# arm_controller_single.net
KiCad netlist of a schematic drawn in EAGLE
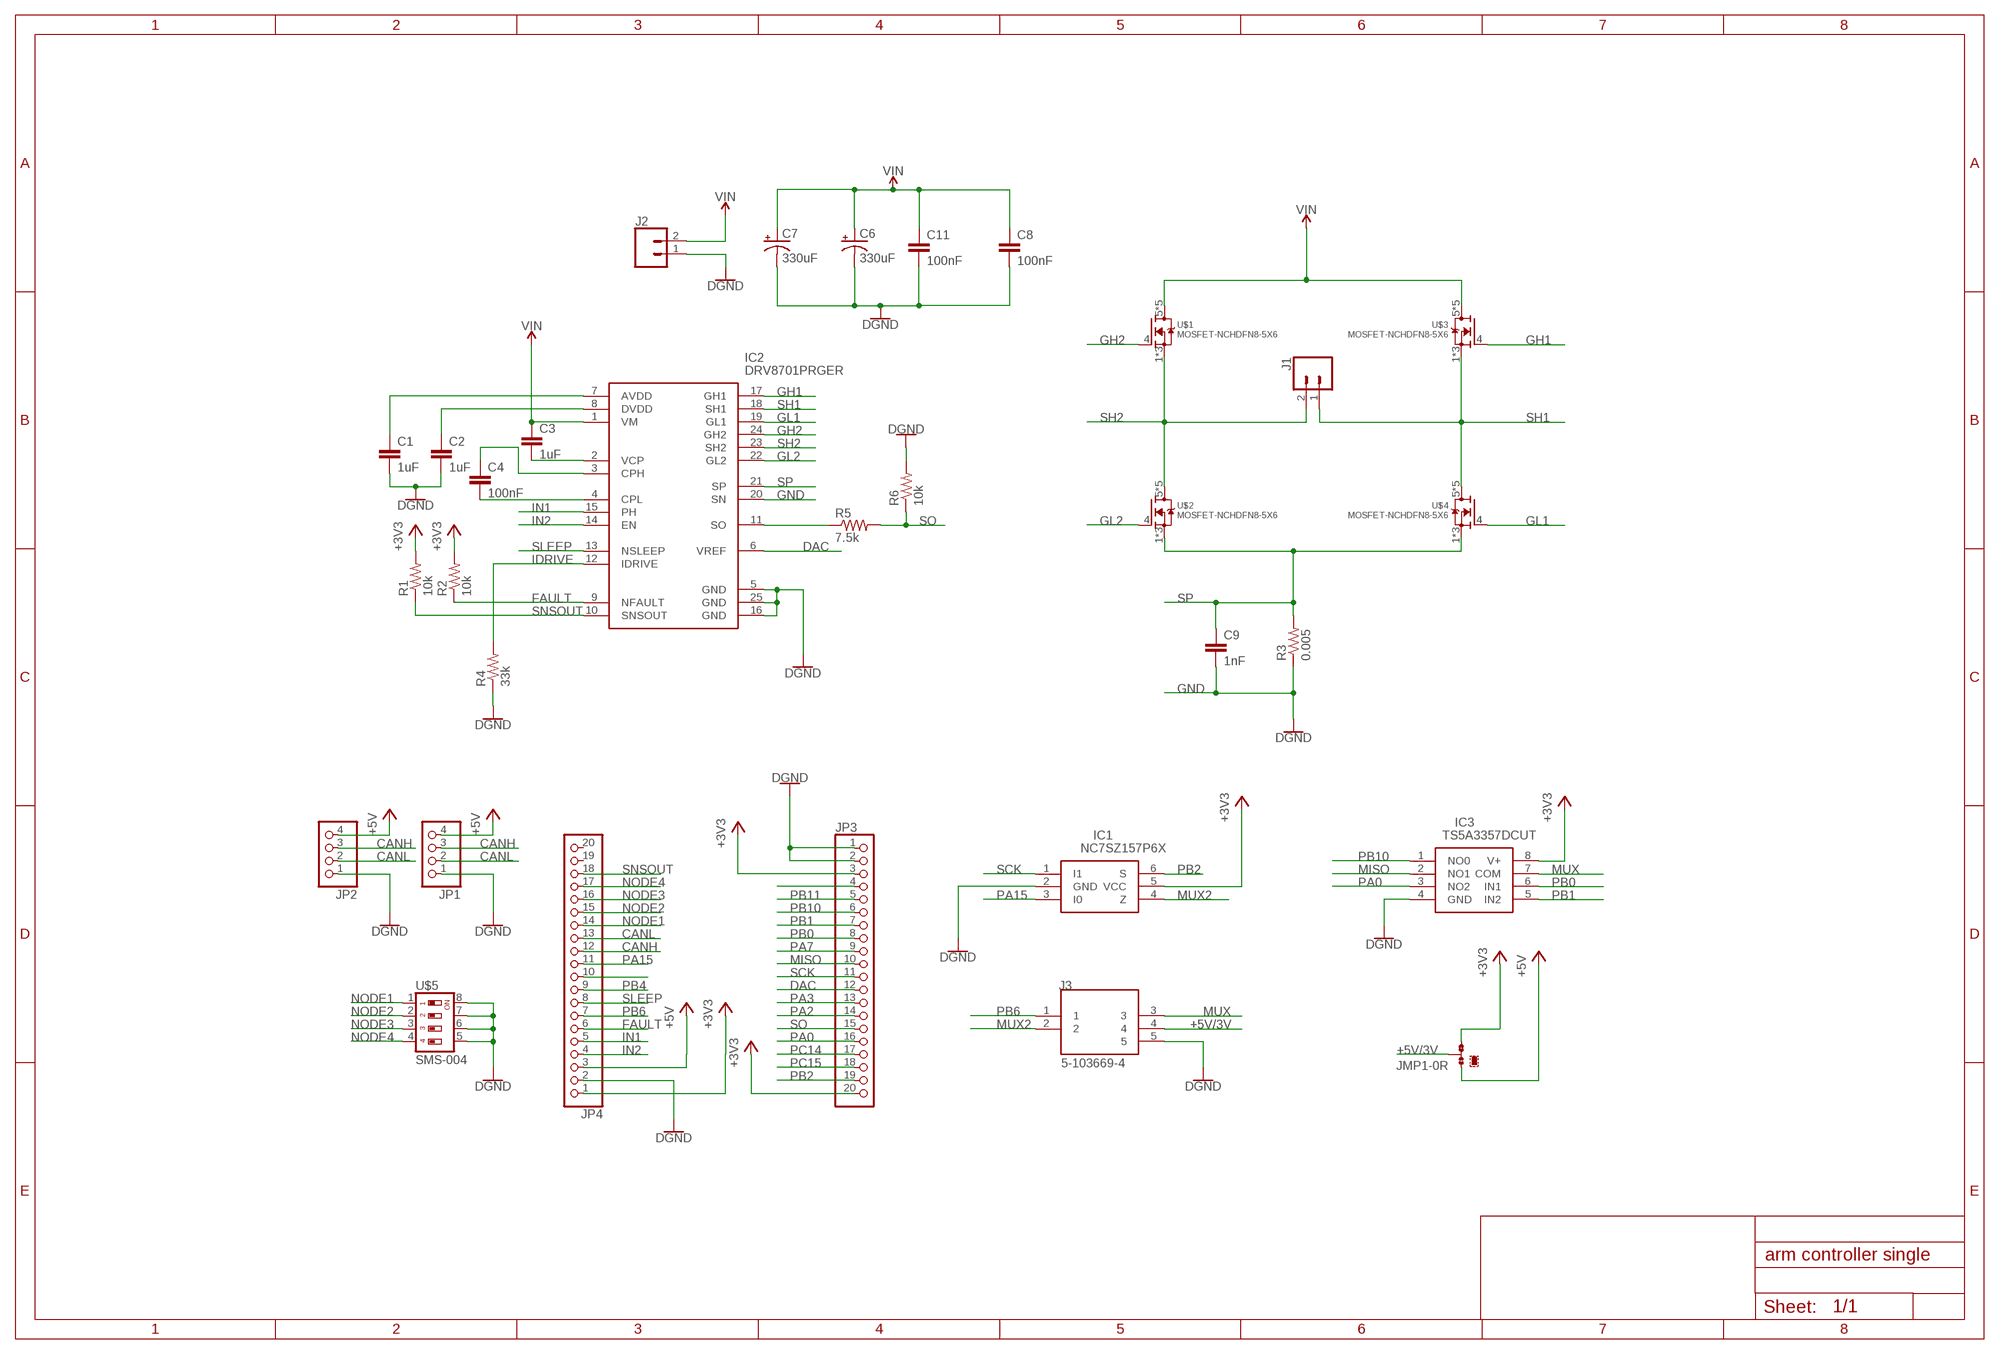
[diagram p0: schematic, sheet 1]

(export (version "E")
  (design (tool "Eeschema 10.0.6"))
  (components
    (comp (ref "C1")
      (value "1uF")
      (footprint "eagle-import:C0805")
      (libsource (lib "eagle-import") (part "C-EUC0805"))
    )
    (comp (ref "C2")
      (value "1uF")
      (footprint "eagle-import:C0805")
      (libsource (lib "eagle-import") (part "C-EUC0805"))
    )
    (comp (ref "C3")
      (value "1uF")
      (footprint "eagle-import:C0805")
      (libsource (lib "eagle-import") (part "C-EUC0805"))
    )
    (comp (ref "C4")
      (value "100nF")
      (footprint "eagle-import:C0805")
      (libsource (lib "eagle-import") (part "C-EUC0805"))
    )
    (comp (ref "C6")
      (value "330uF")
      (footprint "eagle-import:140CLH-1010")
      (libsource (lib "eagle-import") (part "CPOL-US140CLH-1010"))
    )
    (comp (ref "C7")
      (value "330uF")
      (footprint "eagle-import:140CLH-1010")
      (libsource (lib "eagle-import") (part "CPOL-US140CLH-1010"))
    )
    (comp (ref "C8")
      (value "100nF")
      (footprint "eagle-import:C0805")
      (libsource (lib "eagle-import") (part "C-EUC0805"))
    )
    (comp (ref "C9")
      (value "1nF")
      (footprint "eagle-import:C0805")
      (libsource (lib "eagle-import") (part "C-EUC0805"))
    )
    (comp (ref "C11")
      (value "100nF")
      (footprint "eagle-import:C0805")
      (libsource (lib "eagle-import") (part "C-EUC0805"))
    )
    (comp (ref "IC1")
      (value "NC7SZ157P6X")
      (footprint "eagle-import:SOT65P210X110-6N")
      (fields (field (name "MOUSER_PART_NUMBER") "512-NC7SZ157P6X"))
      (libsource (lib "eagle-import") (part "NC7SZ157P6X"))
    )
    (comp (ref "IC2")
      (value "DRV8701PRGER")
      (footprint "eagle-import:QFN50P400X400X100-25N")
      (fields (field (name "MOUSER_PART_NUMBER") "595-DRV8701PRGER"))
      (libsource (lib "eagle-import") (part "DRV8701PRGER"))
    )
    (comp (ref "IC3")
      (value "TS5A3357DCUT")
      (footprint "eagle-import:SOP50P310X90-8N")
      (fields (field (name "MOUSER_PART_NUMBER") "595-TS5A3357DCUT"))
      (libsource (lib "eagle-import") (part "TS5A3357DCUT"))
    )
    (comp (ref "J1")
      (value "CONN_025MM")
      (footprint "eagle-import:SCREWTERMINAL-5MM-2")
      (libsource (lib "eagle-import") (part "CONN_025MM"))
    )
    (comp (ref "J2")
      (value "CONN_025MM")
      (footprint "eagle-import:SCREWTERMINAL-5MM-2")
      (libsource (lib "eagle-import") (part "CONN_025MM"))
    )
    (comp (ref "J3")
      (value "5-103669-4")
      (footprint "eagle-import:TE_5-103669-4")
      (fields (field (name "MF") "TE Connectivity"))
      (libsource (lib "eagle-import") (part "5-103669-4"))
    )
    (comp (ref "JMP1")
      (value "0R-JUMPB")
      (footprint "eagle-import:B0R-JMP")
      (libsource (lib "eagle-import") (part "0R-JUMPB"))
    )
    (comp (ref "JP1")
      (value "PINHD-1X4")
      (footprint "eagle-import:1X04")
      (libsource (lib "eagle-import") (part "PINHD-1X4"))
    )
    (comp (ref "JP2")
      (value "PINHD-1X4")
      (footprint "eagle-import:1X04")
      (libsource (lib "eagle-import") (part "PINHD-1X4"))
    )
    (comp (ref "JP3")
      (value "PINHD-1X20")
      (footprint "eagle-import:1X20")
      (libsource (lib "eagle-import") (part "PINHD-1X20"))
    )
    (comp (ref "JP4")
      (value "PINHD-1X20")
      (footprint "eagle-import:1X20")
      (libsource (lib "eagle-import") (part "PINHD-1X20"))
    )
    (comp (ref "R1")
      (value "10k")
      (footprint "eagle-import:M0805")
      (libsource (lib "eagle-import") (part "R-US_M0805"))
    )
    (comp (ref "R2")
      (value "10k")
      (footprint "eagle-import:M0805")
      (libsource (lib "eagle-import") (part "R-US_M0805"))
    )
    (comp (ref "R3")
      (value "0.005")
      (footprint "eagle-import:WSC4527")
      (libsource (lib "eagle-import") (part "R-US_WSC4527"))
    )
    (comp (ref "R4")
      (value "33k")
      (footprint "eagle-import:M0805")
      (libsource (lib "eagle-import") (part "R-US_M0805"))
    )
    (comp (ref "R5")
      (value "7.5k")
      (footprint "eagle-import:M0805")
      (libsource (lib "eagle-import") (part "R-US_M0805"))
    )
    (comp (ref "R6")
      (value "10k")
      (footprint "eagle-import:M0805")
      (libsource (lib "eagle-import") (part "R-US_M0805"))
    )
    (comp (ref "U$1")
      (value "MOSFET-NCHDFN8-5X6")
      (footprint "eagle-import:ALOM_DFN5X6_8L_EP1_P")
      (libsource (lib "eagle-import") (part "MOSFET-NCHDFN8-5X6"))
    )
    (comp (ref "U$2")
      (value "MOSFET-NCHDFN8-5X6")
      (footprint "eagle-import:ALOM_DFN5X6_8L_EP1_P")
      (libsource (lib "eagle-import") (part "MOSFET-NCHDFN8-5X6"))
    )
    (comp (ref "U$3")
      (value "MOSFET-NCHDFN8-5X6")
      (footprint "eagle-import:ALOM_DFN5X6_8L_EP1_P")
      (libsource (lib "eagle-import") (part "MOSFET-NCHDFN8-5X6"))
    )
    (comp (ref "U$4")
      (value "MOSFET-NCHDFN8-5X6")
      (footprint "eagle-import:ALOM_DFN5X6_8L_EP1_P")
      (libsource (lib "eagle-import") (part "MOSFET-NCHDFN8-5X6"))
    )
    (comp (ref "U$5")
      (value "SMS-004")
      (footprint "eagle-import:SMS-004")
      (libsource (lib "eagle-import") (part "SMS-004"))
    )
  )
  (nets
    (net (code "1") (name "+3V3") (class "Default")
      (node (ref "IC1") (pin "5") (pinfunction "VCC_5") (pintype "power_in"))
      (node (ref "IC3") (pin "8") (pinfunction "V+_8") (pintype "bidirectional"))
      (node (ref "JMP1") (pin "3") (pinfunction "3_3") (pintype "passive"))
      (node (ref "JP3") (pin "20") (pinfunction "20_20") (pintype "passive"))
      (node (ref "JP3") (pin "3") (pinfunction "3_3") (pintype "passive"))
      (node (ref "JP4") (pin "1") (pinfunction "1_1") (pintype "passive"))
      (node (ref "R1") (pin "2") (pinfunction "2_2") (pintype "passive"))
      (node (ref "R2") (pin "2") (pinfunction "2_2") (pintype "passive"))
    )
    (net (code "2") (name "+5V") (class "Default")
      (node (ref "JMP1") (pin "1") (pinfunction "1_1") (pintype "passive"))
      (node (ref "JP1") (pin "4") (pinfunction "4_4") (pintype "passive"))
      (node (ref "JP2") (pin "4") (pinfunction "4_4") (pintype "passive"))
      (node (ref "JP4") (pin "3") (pinfunction "3_3") (pintype "passive"))
    )
    (net (code "3") (name "/+5V{slash}3V") (class "Default")
      (node (ref "J3") (pin "4") (pinfunction "4_4") (pintype "passive"))
      (node (ref "JMP1") (pin "2") (pinfunction "2_2") (pintype "passive"))
    )
    (net (code "4") (name "/CANH") (class "Default")
      (node (ref "JP1") (pin "3") (pinfunction "3_3") (pintype "passive"))
      (node (ref "JP2") (pin "3") (pinfunction "3_3") (pintype "passive"))
      (node (ref "JP4") (pin "12") (pinfunction "12_12") (pintype "passive"))
    )
    (net (code "5") (name "/CANL") (class "Default")
      (node (ref "JP1") (pin "2") (pinfunction "2_2") (pintype "passive"))
      (node (ref "JP2") (pin "2") (pinfunction "2_2") (pintype "passive"))
      (node (ref "JP4") (pin "13") (pinfunction "13_13") (pintype "passive"))
    )
    (net (code "6") (name "/DAC") (class "Default")
      (node (ref "IC2") (pin "6") (pinfunction "VREF_6") (pintype "bidirectional"))
      (node (ref "JP3") (pin "12") (pinfunction "12_12") (pintype "passive"))
    )
    (net (code "7") (name "/FAULT") (class "Default")
      (node (ref "IC2") (pin "9") (pinfunction "NFAULT_9") (pintype "bidirectional"))
      (node (ref "JP4") (pin "6") (pinfunction "6_6") (pintype "passive"))
      (node (ref "R2") (pin "1") (pinfunction "1_1") (pintype "passive"))
    )
    (net (code "8") (name "/GH1") (class "Default")
      (node (ref "IC2") (pin "17") (pinfunction "GH1_17") (pintype "bidirectional"))
      (node (ref "U$3") (pin "4") (pinfunction "G_4") (pintype "bidirectional"))
    )
    (net (code "9") (name "/GH2") (class "Default")
      (node (ref "IC2") (pin "24") (pinfunction "GH2_24") (pintype "bidirectional"))
      (node (ref "U$1") (pin "4") (pinfunction "G_4") (pintype "bidirectional"))
    )
    (net (code "10") (name "/GL1") (class "Default")
      (node (ref "IC2") (pin "19") (pinfunction "GL1_19") (pintype "bidirectional"))
      (node (ref "U$4") (pin "4") (pinfunction "G_4") (pintype "bidirectional"))
    )
    (net (code "11") (name "/GL2") (class "Default")
      (node (ref "IC2") (pin "22") (pinfunction "GL2_22") (pintype "bidirectional"))
      (node (ref "U$2") (pin "4") (pinfunction "G_4") (pintype "bidirectional"))
    )
    (net (code "12") (name "/IDRIVE") (class "Default")
      (node (ref "IC2") (pin "12") (pinfunction "IDRIVE_12") (pintype "bidirectional"))
      (node (ref "R4") (pin "2") (pinfunction "2_2") (pintype "passive"))
    )
    (net (code "13") (name "/IN1") (class "Default")
      (node (ref "IC2") (pin "15") (pinfunction "PH_15") (pintype "bidirectional"))
      (node (ref "JP4") (pin "5") (pinfunction "5_5") (pintype "passive"))
    )
    (net (code "14") (name "/IN2") (class "Default")
      (node (ref "IC2") (pin "14") (pinfunction "EN_14") (pintype "bidirectional"))
      (node (ref "JP4") (pin "4") (pinfunction "4_4") (pintype "passive"))
    )
    (net (code "15") (name "/MISO") (class "Default")
      (node (ref "IC3") (pin "2") (pinfunction "NO1_2") (pintype "bidirectional"))
      (node (ref "JP3") (pin "10") (pinfunction "10_10") (pintype "passive"))
    )
    (net (code "16") (name "/MUX") (class "Default")
      (node (ref "IC3") (pin "7") (pinfunction "COM_7") (pintype "bidirectional"))
      (node (ref "J3") (pin "3") (pinfunction "3_3") (pintype "passive"))
    )
    (net (code "17") (name "/MUX2") (class "Default")
      (node (ref "IC1") (pin "4") (pinfunction "Z_4") (pintype "output"))
      (node (ref "J3") (pin "2") (pinfunction "2_2") (pintype "passive"))
    )
    (net (code "18") (name "/NODE1") (class "Default")
      (node (ref "JP4") (pin "14") (pinfunction "14_14") (pintype "passive"))
      (node (ref "U$5") (pin "1") (pinfunction "1_1") (pintype "passive"))
    )
    (net (code "19") (name "/NODE2") (class "Default")
      (node (ref "JP4") (pin "15") (pinfunction "15_15") (pintype "passive"))
      (node (ref "U$5") (pin "2") (pinfunction "2_2") (pintype "passive"))
    )
    (net (code "20") (name "/NODE3") (class "Default")
      (node (ref "JP4") (pin "16") (pinfunction "16_16") (pintype "passive"))
      (node (ref "U$5") (pin "3") (pinfunction "3_3") (pintype "passive"))
    )
    (net (code "21") (name "/NODE4") (class "Default")
      (node (ref "JP4") (pin "17") (pinfunction "17_17") (pintype "passive"))
      (node (ref "U$5") (pin "4") (pinfunction "4_4") (pintype "passive"))
    )
    (net (code "22") (name "/PA0") (class "Default")
      (node (ref "IC3") (pin "3") (pinfunction "NO2_3") (pintype "bidirectional"))
      (node (ref "JP3") (pin "16") (pinfunction "16_16") (pintype "passive"))
    )
    (net (code "23") (name "/PA2") (class "Default")
      (node (ref "JP3") (pin "14") (pinfunction "14_14") (pintype "passive"))
    )
    (net (code "24") (name "/PA3") (class "Default")
      (node (ref "JP3") (pin "13") (pinfunction "13_13") (pintype "passive"))
    )
    (net (code "25") (name "/PA7") (class "Default")
      (node (ref "JP3") (pin "9") (pinfunction "9_9") (pintype "passive"))
    )
    (net (code "26") (name "/PA15") (class "Default")
      (node (ref "IC1") (pin "3") (pinfunction "I0_3") (pintype "input"))
      (node (ref "JP4") (pin "11") (pinfunction "11_11") (pintype "passive"))
    )
    (net (code "27") (name "/PB0") (class "Default")
      (node (ref "IC3") (pin "6") (pinfunction "IN1_6") (pintype "input"))
      (node (ref "JP3") (pin "8") (pinfunction "8_8") (pintype "passive"))
    )
    (net (code "28") (name "/PB1") (class "Default")
      (node (ref "IC3") (pin "5") (pinfunction "IN2_5") (pintype "input"))
      (node (ref "JP3") (pin "7") (pinfunction "7_7") (pintype "passive"))
    )
    (net (code "29") (name "/PB2") (class "Default")
      (node (ref "IC1") (pin "6") (pinfunction "S_6") (pintype "input"))
      (node (ref "JP3") (pin "19") (pinfunction "19_19") (pintype "passive"))
    )
    (net (code "30") (name "/PB4") (class "Default")
      (node (ref "JP4") (pin "9") (pinfunction "9_9") (pintype "passive"))
    )
    (net (code "31") (name "/PB6") (class "Default")
      (node (ref "J3") (pin "1") (pinfunction "1_1") (pintype "passive"))
      (node (ref "JP4") (pin "7") (pinfunction "7_7") (pintype "passive"))
    )
    (net (code "32") (name "/PB10") (class "Default")
      (node (ref "IC3") (pin "1") (pinfunction "NO0_1") (pintype "bidirectional"))
      (node (ref "JP3") (pin "6") (pinfunction "6_6") (pintype "passive"))
    )
    (net (code "33") (name "/PB11") (class "Default")
      (node (ref "JP3") (pin "5") (pinfunction "5_5") (pintype "passive"))
    )
    (net (code "34") (name "/PC14") (class "Default")
      (node (ref "JP3") (pin "17") (pinfunction "17_17") (pintype "passive"))
    )
    (net (code "35") (name "/PC15") (class "Default")
      (node (ref "JP3") (pin "18") (pinfunction "18_18") (pintype "passive"))
    )
    (net (code "36") (name "/SCK") (class "Default")
      (node (ref "IC1") (pin "1") (pinfunction "I1_1") (pintype "input"))
      (node (ref "JP3") (pin "11") (pinfunction "11_11") (pintype "passive"))
    )
    (net (code "37") (name "/SH1") (class "Default")
      (node (ref "IC2") (pin "18") (pinfunction "SH1_18") (pintype "bidirectional"))
      (node (ref "J1") (pin "1") (pinfunction "1_1") (pintype "passive"))
      (node (ref "U$3") (pin "1") (pinfunction "S_1") (pintype "bidirectional"))
      (node (ref "U$3") (pin "2") (pinfunction "S_2") (pintype "bidirectional"))
      (node (ref "U$3") (pin "3") (pinfunction "S_3") (pintype "bidirectional"))
      (node (ref "U$4") (pin "5") (pinfunction "D_5") (pintype "bidirectional"))
      (node (ref "U$4") (pin "6") (pinfunction "D_6") (pintype "bidirectional"))
      (node (ref "U$4") (pin "7") (pinfunction "D_7") (pintype "bidirectional"))
      (node (ref "U$4") (pin "8") (pinfunction "D_8") (pintype "bidirectional"))
      (node (ref "U$4") (pin "9") (pinfunction "D_9") (pintype "bidirectional"))
    )
    (net (code "38") (name "/SH2") (class "Default")
      (node (ref "IC2") (pin "23") (pinfunction "SH2_23") (pintype "bidirectional"))
      (node (ref "J1") (pin "2") (pinfunction "2_2") (pintype "passive"))
      (node (ref "U$1") (pin "1") (pinfunction "S_1") (pintype "bidirectional"))
      (node (ref "U$1") (pin "2") (pinfunction "S_2") (pintype "bidirectional"))
      (node (ref "U$1") (pin "3") (pinfunction "S_3") (pintype "bidirectional"))
      (node (ref "U$2") (pin "5") (pinfunction "D_5") (pintype "bidirectional"))
      (node (ref "U$2") (pin "6") (pinfunction "D_6") (pintype "bidirectional"))
      (node (ref "U$2") (pin "7") (pinfunction "D_7") (pintype "bidirectional"))
      (node (ref "U$2") (pin "8") (pinfunction "D_8") (pintype "bidirectional"))
      (node (ref "U$2") (pin "9") (pinfunction "D_9") (pintype "bidirectional"))
    )
    (net (code "39") (name "/SLEEP") (class "Default")
      (node (ref "IC2") (pin "13") (pinfunction "NSLEEP_13") (pintype "bidirectional"))
      (node (ref "JP4") (pin "8") (pinfunction "8_8") (pintype "passive"))
    )
    (net (code "40") (name "/SNSOUT") (class "Default")
      (node (ref "IC2") (pin "10") (pinfunction "SNSOUT_10") (pintype "bidirectional"))
      (node (ref "JP4") (pin "18") (pinfunction "18_18") (pintype "passive"))
      (node (ref "R1") (pin "1") (pinfunction "1_1") (pintype "passive"))
    )
    (net (code "41") (name "/SO") (class "Default")
      (node (ref "JP3") (pin "15") (pinfunction "15_15") (pintype "passive"))
      (node (ref "R5") (pin "2") (pinfunction "2_2") (pintype "passive"))
      (node (ref "R6") (pin "1") (pinfunction "1_1") (pintype "passive"))
    )
    (net (code "42") (name "/SP") (class "Default")
      (node (ref "C9") (pin "1") (pinfunction "1_1") (pintype "passive"))
      (node (ref "IC2") (pin "21") (pinfunction "SP_21") (pintype "bidirectional"))
      (node (ref "R3") (pin "2") (pinfunction "2_2") (pintype "passive"))
      (node (ref "U$2") (pin "1") (pinfunction "S_1") (pintype "bidirectional"))
      (node (ref "U$2") (pin "2") (pinfunction "S_2") (pintype "bidirectional"))
      (node (ref "U$2") (pin "3") (pinfunction "S_3") (pintype "bidirectional"))
      (node (ref "U$4") (pin "1") (pinfunction "S_1") (pintype "bidirectional"))
      (node (ref "U$4") (pin "2") (pinfunction "S_2") (pintype "bidirectional"))
      (node (ref "U$4") (pin "3") (pinfunction "S_3") (pintype "bidirectional"))
    )
    (net (code "43") (name "DGND") (class "Default")
      (node (ref "C1") (pin "2") (pinfunction "2_2") (pintype "passive"))
      (node (ref "C11") (pin "2") (pinfunction "2_2") (pintype "passive"))
      (node (ref "C2") (pin "2") (pinfunction "2_2") (pintype "passive"))
      (node (ref "C6") (pin "-") (pinfunction "-_-") (pintype "passive"))
      (node (ref "C7") (pin "-") (pinfunction "-_-") (pintype "passive"))
      (node (ref "C8") (pin "2") (pinfunction "2_2") (pintype "passive"))
      (node (ref "C9") (pin "2") (pinfunction "2_2") (pintype "passive"))
      (node (ref "IC1") (pin "2") (pinfunction "GND_2") (pintype "power_in"))
      (node (ref "IC2") (pin "16") (pinfunction "GND_16") (pintype "bidirectional"))
      (node (ref "IC2") (pin "20") (pinfunction "SN_20") (pintype "bidirectional"))
      (node (ref "IC2") (pin "25") (pinfunction "GND_25") (pintype "bidirectional"))
      (node (ref "IC2") (pin "5") (pinfunction "GND_5") (pintype "bidirectional"))
      (node (ref "IC3") (pin "4") (pinfunction "GND_4") (pintype "power_in"))
      (node (ref "J2") (pin "1") (pinfunction "1_1") (pintype "passive"))
      (node (ref "J3") (pin "5") (pinfunction "5_5") (pintype "passive"))
      (node (ref "JP1") (pin "1") (pinfunction "1_1") (pintype "passive"))
      (node (ref "JP2") (pin "1") (pinfunction "1_1") (pintype "passive"))
      (node (ref "JP3") (pin "1") (pinfunction "1_1") (pintype "passive"))
      (node (ref "JP3") (pin "2") (pinfunction "2_2") (pintype "passive"))
      (node (ref "JP4") (pin "2") (pinfunction "2_2") (pintype "passive"))
      (node (ref "R3") (pin "1") (pinfunction "1_1") (pintype "passive"))
      (node (ref "R4") (pin "1") (pinfunction "1_1") (pintype "passive"))
      (node (ref "R6") (pin "2") (pinfunction "2_2") (pintype "passive"))
      (node (ref "U$5") (pin "5") (pinfunction "5_5") (pintype "passive"))
      (node (ref "U$5") (pin "6") (pinfunction "6_6") (pintype "passive"))
      (node (ref "U$5") (pin "7") (pinfunction "7_7") (pintype "passive"))
      (node (ref "U$5") (pin "8") (pinfunction "8_8") (pintype "passive"))
    )
    (net (code "44") (name "Net-(IC2-AVDD)") (class "Default")
      (node (ref "C1") (pin "1") (pinfunction "1_1") (pintype "passive"))
      (node (ref "IC2") (pin "7") (pinfunction "AVDD_7") (pintype "bidirectional"))
    )
    (net (code "45") (name "Net-(IC2-CPH)") (class "Default")
      (node (ref "C4") (pin "1") (pinfunction "1_1") (pintype "passive"))
      (node (ref "IC2") (pin "3") (pinfunction "CPH_3") (pintype "bidirectional"))
    )
    (net (code "46") (name "Net-(IC2-CPL)") (class "Default")
      (node (ref "C4") (pin "2") (pinfunction "2_2") (pintype "passive"))
      (node (ref "IC2") (pin "4") (pinfunction "CPL_4") (pintype "bidirectional"))
    )
    (net (code "47") (name "Net-(IC2-DVDD)") (class "Default")
      (node (ref "C2") (pin "1") (pinfunction "1_1") (pintype "passive"))
      (node (ref "IC2") (pin "8") (pinfunction "DVDD_8") (pintype "bidirectional"))
    )
    (net (code "48") (name "Net-(IC2-SO)") (class "Default")
      (node (ref "IC2") (pin "11") (pinfunction "SO_11") (pintype "bidirectional"))
      (node (ref "R5") (pin "1") (pinfunction "1_1") (pintype "passive"))
    )
    (net (code "49") (name "Net-(IC2-VCP)") (class "Default")
      (node (ref "C3") (pin "2") (pinfunction "2_2") (pintype "passive"))
      (node (ref "IC2") (pin "2") (pinfunction "VCP_2") (pintype "bidirectional"))
    )
    (net (code "50") (name "VIN") (class "Default")
      (node (ref "C11") (pin "1") (pinfunction "1_1") (pintype "passive"))
      (node (ref "C3") (pin "1") (pinfunction "1_1") (pintype "passive"))
      (node (ref "C6") (pin "+") (pinfunction "+_+") (pintype "passive"))
      (node (ref "C7") (pin "+") (pinfunction "+_+") (pintype "passive"))
      (node (ref "C8") (pin "1") (pinfunction "1_1") (pintype "passive"))
      (node (ref "IC2") (pin "1") (pinfunction "VM_1") (pintype "bidirectional"))
      (node (ref "J2") (pin "2") (pinfunction "2_2") (pintype "passive"))
      (node (ref "U$1") (pin "5") (pinfunction "D_5") (pintype "bidirectional"))
      (node (ref "U$1") (pin "6") (pinfunction "D_6") (pintype "bidirectional"))
      (node (ref "U$1") (pin "7") (pinfunction "D_7") (pintype "bidirectional"))
      (node (ref "U$1") (pin "8") (pinfunction "D_8") (pintype "bidirectional"))
      (node (ref "U$1") (pin "9") (pinfunction "D_9") (pintype "bidirectional"))
      (node (ref "U$3") (pin "5") (pinfunction "D_5") (pintype "bidirectional"))
      (node (ref "U$3") (pin "6") (pinfunction "D_6") (pintype "bidirectional"))
      (node (ref "U$3") (pin "7") (pinfunction "D_7") (pintype "bidirectional"))
      (node (ref "U$3") (pin "8") (pinfunction "D_8") (pintype "bidirectional"))
      (node (ref "U$3") (pin "9") (pinfunction "D_9") (pintype "bidirectional"))
    )
    (net (code "51") (name "unconnected-(JP3-Pad4)") (class "Default")
      (node (ref "JP3") (pin "4") (pinfunction "4_4") (pintype "passive"))
    )
    (net (code "52") (name "unconnected-(JP4-Pad10)") (class "Default")
      (node (ref "JP4") (pin "10") (pinfunction "10_10") (pintype "passive"))
    )
    (net (code "53") (name "unconnected-(JP4-Pad19)") (class "Default")
      (node (ref "JP4") (pin "19") (pinfunction "19_19") (pintype "passive"))
    )
    (net (code "54") (name "unconnected-(JP4-Pad20)") (class "Default")
      (node (ref "JP4") (pin "20") (pinfunction "20_20") (pintype "passive"))
    )
  )
)
